# Misc.net
KiCad netlist of a schematic drawn in Altium Designer
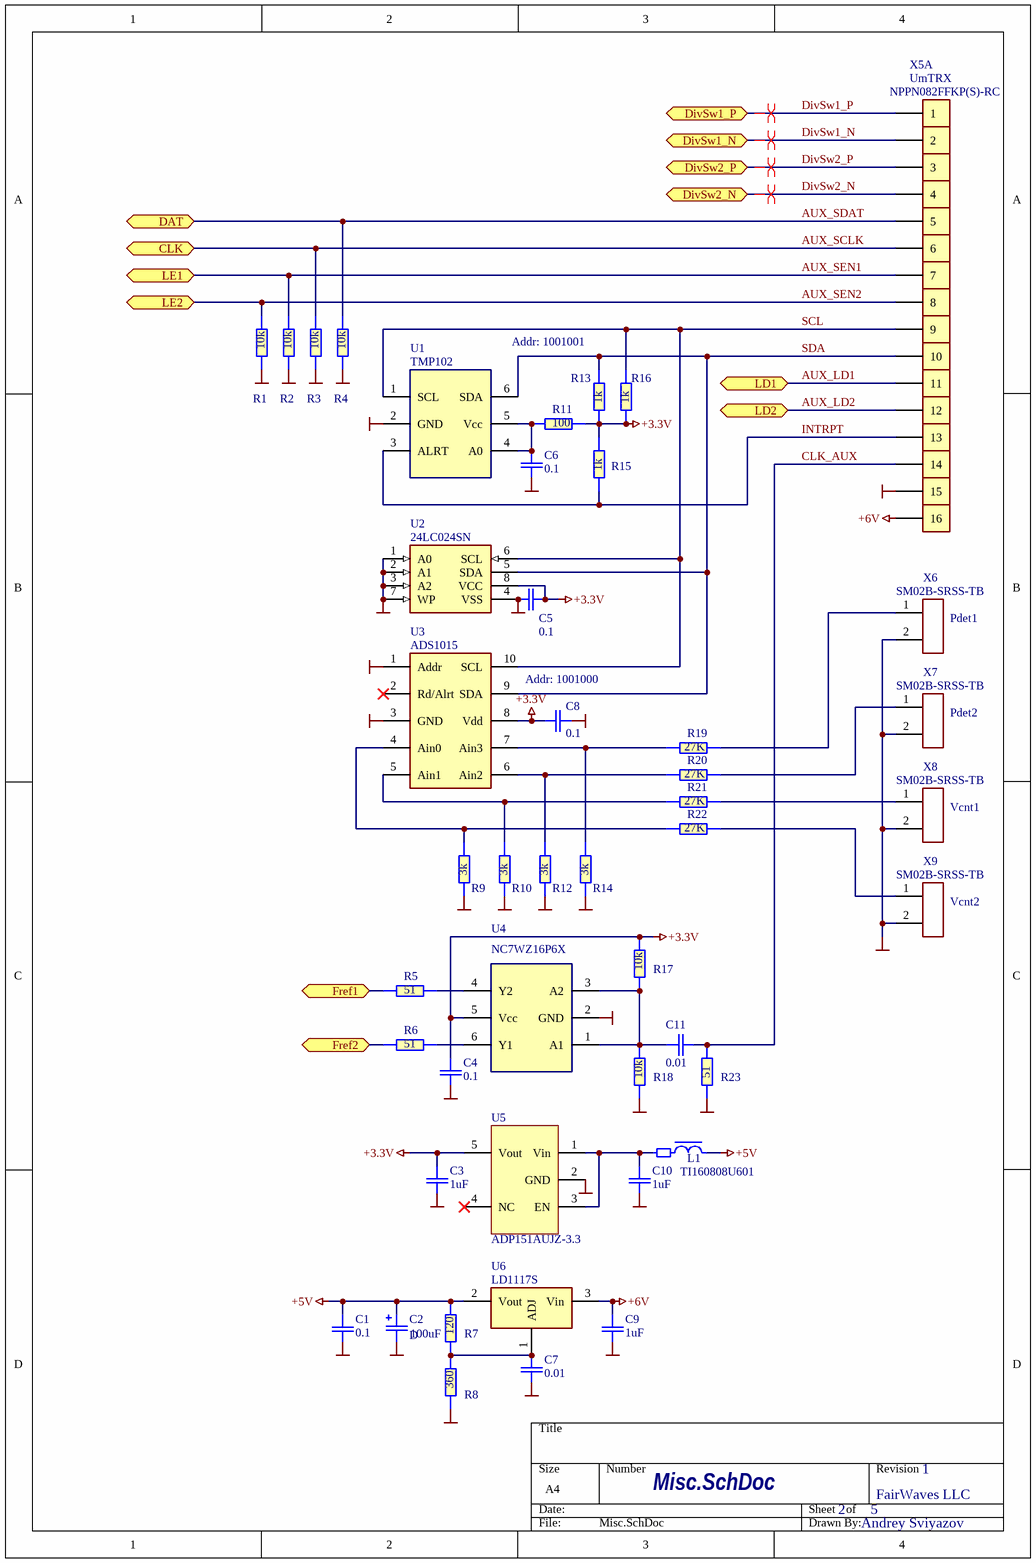
[diagram p0: Misc.SchDoc]

(export (version "E")
  (design (tool "Eeschema 10.0.6"))
  (components
    (comp (ref "C1")
      (value "0.1")
      (footprint "C0603-Phillips")
      (description "Capacitor")
      (fields (field (name "MANUFACTURER") "MURATA") (field (name "TOLERANCE") "20%"))
      (libsource (lib "Capacitors") (part "C0603"))
    )
    (comp (ref "C2")
      (value "100uF")
      (footprint "cd7343")
      (description "Capacitor")
      (fields (field (name "MANUFACTURER") "SPRAGUE"))
      (libsource (lib "altium-import") (part "root_0_mirrored_CD7343_"))
    )
    (comp (ref "C3")
      (value "1uF")
      (footprint "C0603-Phillips")
      (description "Capacitor")
      (fields (field (name "MANUFACTURER") "MURATA") (field (name "TOLERANCE") "20%"))
      (libsource (lib "Capacitors") (part "C0603"))
    )
    (comp (ref "C4")
      (value "0.1")
      (footprint "C0603-Phillips")
      (description "Capacitor")
      (fields (field (name "MANUFACTURER") "MURATA") (field (name "TOLERANCE") "20%"))
      (libsource (lib "Capacitors") (part "C0603"))
    )
    (comp (ref "C5")
      (value "0.1")
      (footprint "C0603-Phillips")
      (description "Capacitor")
      (fields (field (name "MANUFACTURER") "MURATA") (field (name "TOLERANCE") "20%"))
      (libsource (lib "Capacitors") (part "C0603"))
    )
    (comp (ref "C6")
      (value "0.1")
      (footprint "C0603-Phillips")
      (description "Capacitor")
      (fields (field (name "MANUFACTURER") "MURATA") (field (name "TOLERANCE") "20%"))
      (libsource (lib "Capacitors") (part "C0603"))
    )
    (comp (ref "C7")
      (value "0.01")
      (footprint "C0603-Phillips")
      (description "Capacitor")
      (fields (field (name "MANUFACTURER") "MURATA") (field (name "TOLERANCE") "20%"))
      (libsource (lib "Capacitors") (part "C0603"))
    )
    (comp (ref "C8")
      (value "0.1")
      (footprint "C0603-Phillips")
      (description "Capacitor")
      (fields (field (name "MANUFACTURER") "MURATA") (field (name "TOLERANCE") "20%"))
      (libsource (lib "Capacitors") (part "C0603"))
    )
    (comp (ref "C9")
      (value "1uF")
      (footprint "C0603-Phillips")
      (description "Capacitor")
      (fields (field (name "MANUFACTURER") "MURATA") (field (name "TOLERANCE") "20%"))
      (libsource (lib "Capacitors") (part "C0603"))
    )
    (comp (ref "C10")
      (value "1uF")
      (footprint "C0603-Phillips")
      (description "Capacitor")
      (fields (field (name "MANUFACTURER") "MURATA") (field (name "TOLERANCE") "20%"))
      (libsource (lib "Capacitors") (part "C0603"))
    )
    (comp (ref "C11")
      (value "0.01")
      (footprint "C0603-Phillips")
      (description "Capacitor")
      (fields (field (name "MANUFACTURER") "MURATA") (field (name "TOLERANCE") "20%"))
      (libsource (lib "Capacitors") (part "C0603"))
    )
    (comp (ref "L1")
      (value "TI160808U601")
      (footprint "Andy:Ti160808-Phillips")
      (description "Choke")
      (fields (field (name "MANUFACTURER") "MURATA"))
      (libsource (lib "altium-import") (part "root_0_mirrored_TI160808_"))
    )
    (comp (ref "R1")
      (value "10k")
      (footprint "R0603-PHILLIPS")
      (description "Resistor")
      (fields (field (name "MANUFACTURER") "YAGEO") (field (name "TOLERANCE") "5%"))
      (libsource (lib "altium-import") (part "root_2_R0603_"))
    )
    (comp (ref "R2")
      (value "10k")
      (footprint "R0603-PHILLIPS")
      (description "Resistor")
      (fields (field (name "MANUFACTURER") "YAGEO") (field (name "TOLERANCE") "5%"))
      (libsource (lib "altium-import") (part "root_2_R0603_"))
    )
    (comp (ref "R3")
      (value "10k")
      (footprint "R0603-PHILLIPS")
      (description "Resistor")
      (fields (field (name "MANUFACTURER") "YAGEO") (field (name "TOLERANCE") "5%"))
      (libsource (lib "altium-import") (part "root_2_R0603_"))
    )
    (comp (ref "R4")
      (value "10k")
      (footprint "R0603-PHILLIPS")
      (description "Resistor")
      (fields (field (name "MANUFACTURER") "YAGEO") (field (name "TOLERANCE") "5%"))
      (libsource (lib "altium-import") (part "root_2_R0603_"))
    )
    (comp (ref "R5")
      (value "51")
      (footprint "R0603-PHILLIPS")
      (description "Resistor")
      (fields (field (name "MANUFACTURER") "YAGEO") (field (name "TOLERANCE") "5%"))
      (libsource (lib "altium-import") (part "root_1_R0603_"))
    )
    (comp (ref "R6")
      (value "51")
      (footprint "R0603-PHILLIPS")
      (description "Resistor")
      (fields (field (name "MANUFACTURER") "YAGEO") (field (name "TOLERANCE") "5%"))
      (libsource (lib "altium-import") (part "root_1_R0603_"))
    )
    (comp (ref "R7")
      (value "120")
      (footprint "R0603-PHILLIPS")
      (description "Resistor")
      (fields (field (name "MANUFACTURER") "YAGEO") (field (name "TOLERANCE") "5%"))
      (libsource (lib "altium-import") (part "root_0_mirrored_R0603_"))
    )
    (comp (ref "R8")
      (value "360")
      (footprint "R0603-PHILLIPS")
      (description "Resistor")
      (fields (field (name "MANUFACTURER") "YAGEO") (field (name "TOLERANCE") "5%"))
      (libsource (lib "altium-import") (part "root_0_mirrored_R0603_"))
    )
    (comp (ref "R9")
      (value "3k")
      (footprint "R0603-PHILLIPS")
      (description "Resistor")
      (fields (field (name "MANUFACTURER") "YAGEO") (field (name "TOLERANCE") "1%"))
      (libsource (lib "altium-import") (part "root_0_mirrored_R0603_"))
    )
    (comp (ref "R10")
      (value "3k")
      (footprint "R0603-PHILLIPS")
      (description "Resistor")
      (fields (field (name "MANUFACTURER") "YAGEO") (field (name "TOLERANCE") "1%"))
      (libsource (lib "altium-import") (part "root_0_mirrored_R0603_"))
    )
    (comp (ref "R11")
      (value "100")
      (footprint "R0603-PHILLIPS")
      (description "Resistor")
      (fields (field (name "MANUFACTURER") "YAGEO") (field (name "TOLERANCE") "5%"))
      (libsource (lib "altium-import") (part "root_1_R0603_"))
    )
    (comp (ref "R12")
      (value "3k")
      (footprint "R0603-PHILLIPS")
      (description "Resistor")
      (fields (field (name "MANUFACTURER") "YAGEO") (field (name "TOLERANCE") "1%"))
      (libsource (lib "altium-import") (part "root_0_mirrored_R0603_"))
    )
    (comp (ref "R13")
      (value "1k")
      (footprint "R0603-PHILLIPS")
      (description "Resistor")
      (fields (field (name "MANUFACTURER") "YAGEO") (field (name "TOLERANCE") "5%"))
      (libsource (lib "altium-import") (part "root_2_R0603_"))
    )
    (comp (ref "R14")
      (value "3k")
      (footprint "R0603-PHILLIPS")
      (description "Resistor")
      (fields (field (name "MANUFACTURER") "YAGEO") (field (name "TOLERANCE") "1%"))
      (libsource (lib "altium-import") (part "root_0_mirrored_R0603_"))
    )
    (comp (ref "R15")
      (value "1k")
      (footprint "R0603-PHILLIPS")
      (description "Resistor")
      (fields (field (name "MANUFACTURER") "YAGEO") (field (name "TOLERANCE") "5%"))
      (libsource (lib "altium-import") (part "root_2_R0603_"))
    )
    (comp (ref "R16")
      (value "1k")
      (footprint "R0603-PHILLIPS")
      (description "Resistor")
      (fields (field (name "MANUFACTURER") "YAGEO") (field (name "TOLERANCE") "5%"))
      (libsource (lib "altium-import") (part "root_2_R0603_"))
    )
    (comp (ref "R17")
      (value "10k")
      (footprint "R0603-PHILLIPS")
      (description "Resistor")
      (fields (field (name "MANUFACTURER") "YAGEO") (field (name "TOLERANCE") "5%"))
      (libsource (lib "altium-import") (part "root_0_mirrored_R0603_"))
    )
    (comp (ref "R18")
      (value "10k")
      (footprint "R0603-PHILLIPS")
      (description "Resistor")
      (fields (field (name "MANUFACTURER") "YAGEO") (field (name "TOLERANCE") "5%"))
      (libsource (lib "altium-import") (part "root_0_mirrored_R0603_"))
    )
    (comp (ref "R19")
      (value "27K")
      (footprint "R0603-PHILLIPS")
      (description "Resistor")
      (fields (field (name "MANUFACTURER") "YAGEO") (field (name "TOLERANCE") "1%"))
      (libsource (lib "altium-import") (part "root_1_R0603_"))
    )
    (comp (ref "R20")
      (value "27K")
      (footprint "R0603-PHILLIPS")
      (description "Resistor")
      (fields (field (name "MANUFACTURER") "YAGEO") (field (name "TOLERANCE") "1%"))
      (libsource (lib "altium-import") (part "root_1_R0603_"))
    )
    (comp (ref "R21")
      (value "27K")
      (footprint "R0603-PHILLIPS")
      (description "Resistor")
      (fields (field (name "MANUFACTURER") "YAGEO") (field (name "TOLERANCE") "1%"))
      (libsource (lib "altium-import") (part "root_1_R0603_"))
    )
    (comp (ref "R22")
      (value "27K")
      (footprint "R0603-PHILLIPS")
      (description "Resistor")
      (fields (field (name "MANUFACTURER") "YAGEO") (field (name "TOLERANCE") "1%"))
      (libsource (lib "altium-import") (part "root_1_R0603_"))
    )
    (comp (ref "R23")
      (value "51")
      (footprint "R0603-PHILLIPS")
      (description "Resistor")
      (fields (field (name "MANUFACTURER") "YAGEO") (field (name "TOLERANCE") "5%"))
      (libsource (lib "altium-import") (part "root_0_mirrored_R0603_"))
    )
    (comp (ref "U1")
      (value "TMP102")
      (footprint "PDSO-G6")
      (description "IC")
      (fields (field (name "MANUFACTURER") "TI") (field (name "ADDR") "1001001"))
      (libsource (lib "Andy") (part "TMP102"))
    )
    (comp (ref "U2")
      (value "24LC024SN")
      (footprint "FootSO-DIP:SOIC8")
      (description "EEPROM")
      (fields (field (name "MANUFACTURER") "Microchip"))
      (libsource (lib "MicroCircuits0-L") (part "AT24CXX"))
    )
    (comp (ref "U3")
      (value "ADS1015")
      (footprint "TSSOP-SPDSO-G10")
      (description "IC")
      (fields (field (name "MANUFACTURER") "TI") (field (name "ADDR") "1001000"))
      (libsource (lib "Andy") (part "ADS1015"))
    )
    (comp (ref "U4")
      (value "NC7WZ16P6X")
      (footprint "SC70-6LD(SOT363)")
      (description "IC")
      (fields (field (name "MANUFACTURER") "Fairchild"))
      (libsource (lib "Andy") (part "NC7WZ16P6X"))
    )
    (comp (ref "U5")
      (value "ADP151AUJZ-3.3")
      (footprint "SOT-23-5[3.1x1.8/0.95]")
      (description "IC")
      (fields (field (name "MANUFACTURER") "AD"))
      (libsource (lib "Andy") (part "ADP151AUJZ"))
    )
    (comp (ref "U6")
      (value "LD1117S")
      (footprint "Foot3-4pins:SOT-223-1")
      (description "IC")
      (fields (field (name "MANUFACTURER") "STMicro"))
      (libsource (lib "altium-import") (part "root_0_mirrored_LD1117ADJ_"))
    )
    (comp (ref "X5")
      (value "NPPN082FFKP(S)-RC")
      (footprint "NPPN082FFKP(S)")
      (description "Connector female 2mm SMD")
      (fields (field (name "MANUFACTURER") "Sullins") (field (name "MISC") "UmTRX"))
      (libsource (lib "Andy") (part "NPPN082FFKP(S)"))
    )
    (comp (ref "X6")
      (value "SM02B-SRSS-TB")
      (footprint "SM02B-SRSS-TB")
      (description "Connector")
      (fields (field (name "MANUFACTURER") "JST") (field (name "MISC") "Pdet1"))
      (libsource (lib "Andy") (part "SM02B-SRSS-TB"))
    )
    (comp (ref "X7")
      (value "SM02B-SRSS-TB")
      (footprint "SM02B-SRSS-TB")
      (description "Connector")
      (fields (field (name "MANUFACTURER") "JST") (field (name "MISC") "Pdet2"))
      (libsource (lib "Andy") (part "SM02B-SRSS-TB"))
    )
    (comp (ref "X8")
      (value "SM02B-SRSS-TB")
      (footprint "SM02B-SRSS-TB")
      (description "Connector")
      (fields (field (name "MANUFACTURER") "JST") (field (name "MISC") "Vcnt1"))
      (libsource (lib "Andy") (part "SM02B-SRSS-TB"))
    )
    (comp (ref "X9")
      (value "SM02B-SRSS-TB")
      (footprint "SM02B-SRSS-TB")
      (description "Connector")
      (fields (field (name "MANUFACTURER") "JST") (field (name "MISC") "Vcnt2"))
      (libsource (lib "Andy") (part "SM02B-SRSS-TB"))
    )
  )
  (nets
    (net (code "1") (name "+3.3V") (class "Default")
      (node (ref "C3") (pin "2") (pinfunction "2_2") (pintype "passive"))
      (node (ref "C4") (pin "2") (pinfunction "2_2") (pintype "passive"))
      (node (ref "C5") (pin "2") (pinfunction "2_2") (pintype "passive"))
      (node (ref "C8") (pin "1") (pinfunction "1_1") (pintype "passive"))
      (node (ref "R11") (pin "2") (pinfunction "2_2") (pintype "passive"))
      (node (ref "R13") (pin "1") (pinfunction "1_1") (pintype "passive"))
      (node (ref "R15") (pin "2") (pinfunction "2_2") (pintype "passive"))
      (node (ref "R16") (pin "1") (pinfunction "1_1") (pintype "passive"))
      (node (ref "R17") (pin "1") (pinfunction "1_1") (pintype "passive"))
      (node (ref "U2") (pin "8") (pinfunction "VCC_8") (pintype "power_in"))
      (node (ref "U3") (pin "8") (pinfunction "Vdd_8") (pintype "passive"))
      (node (ref "U4") (pin "5") (pinfunction "Vcc_5") (pintype "passive"))
      (node (ref "U5") (pin "5") (pinfunction "Vout_5") (pintype "passive"))
    )
    (net (code "2") (name "+5V") (class "Default")
      (node (ref "C1") (pin "2") (pinfunction "2_2") (pintype "passive"))
      (node (ref "C2") (pin "1") (pinfunction "+_1") (pintype "passive"))
      (node (ref "L1") (pin "1") (pinfunction "1_1") (pintype "passive"))
      (node (ref "R7") (pin "1") (pinfunction "1_1") (pintype "passive"))
      (node (ref "U6") (pin "2") (pinfunction "Vout_2") (pintype "passive"))
    )
    (net (code "3") (name "+6V") (class "Default")
      (node (ref "C9") (pin "2") (pinfunction "2_2") (pintype "passive"))
      (node (ref "U6") (pin "3") (pinfunction "Vin_3") (pintype "passive"))
      (node (ref "X5") (pin "16") (pinfunction "16_16") (pintype "passive"))
    )
    (net (code "4") (name "/AUX_LD1") (class "Default")
      (node (ref "X5") (pin "11") (pinfunction "11_11") (pintype "passive"))
    )
    (net (code "5") (name "/AUX_LD2") (class "Default")
      (node (ref "X5") (pin "12") (pinfunction "12_12") (pintype "passive"))
    )
    (net (code "6") (name "/AUX_SCLK") (class "Default")
      (node (ref "R3") (pin "2") (pinfunction "2_2") (pintype "passive"))
      (node (ref "X5") (pin "6") (pinfunction "6_6") (pintype "passive"))
    )
    (net (code "7") (name "/AUX_SDAT") (class "Default")
      (node (ref "R4") (pin "2") (pinfunction "2_2") (pintype "passive"))
      (node (ref "X5") (pin "5") (pinfunction "5_5") (pintype "passive"))
    )
    (net (code "8") (name "/AUX_SEN1") (class "Default")
      (node (ref "R2") (pin "2") (pinfunction "2_2") (pintype "passive"))
      (node (ref "X5") (pin "7") (pinfunction "7_7") (pintype "passive"))
    )
    (net (code "9") (name "/AUX_SEN2") (class "Default")
      (node (ref "R1") (pin "2") (pinfunction "2_2") (pintype "passive"))
      (node (ref "X5") (pin "8") (pinfunction "8_8") (pintype "passive"))
    )
    (net (code "10") (name "/CLK_AUX") (class "Default")
      (node (ref "C11") (pin "1") (pinfunction "1_1") (pintype "passive"))
      (node (ref "R23") (pin "1") (pinfunction "1_1") (pintype "passive"))
      (node (ref "X5") (pin "14") (pinfunction "14_14") (pintype "passive"))
    )
    (net (code "11") (name "/DivSw1_N") (class "Default")
      (node (ref "X5") (pin "2") (pinfunction "2_2") (pintype "passive"))
    )
    (net (code "12") (name "/DivSw1_P") (class "Default")
      (node (ref "X5") (pin "1") (pinfunction "1_1") (pintype "passive"))
    )
    (net (code "13") (name "/DivSw2_N") (class "Default")
      (node (ref "X5") (pin "4") (pinfunction "4_4") (pintype "passive"))
    )
    (net (code "14") (name "/DivSw2_P") (class "Default")
      (node (ref "X5") (pin "3") (pinfunction "3_3") (pintype "passive"))
    )
    (net (code "15") (name "/Fref1") (class "Default")
      (node (ref "R5") (pin "1") (pinfunction "1_1") (pintype "passive"))
    )
    (net (code "16") (name "/Fref2") (class "Default")
      (node (ref "R6") (pin "1") (pinfunction "1_1") (pintype "passive"))
    )
    (net (code "17") (name "/INTRPT") (class "Default")
      (node (ref "R15") (pin "1") (pinfunction "1_1") (pintype "passive"))
      (node (ref "U1") (pin "3") (pinfunction "ALRT_3") (pintype "passive"))
      (node (ref "X5") (pin "13") (pinfunction "13_13") (pintype "passive"))
    )
    (net (code "18") (name "/SCL") (class "Default")
      (node (ref "R16") (pin "2") (pinfunction "2_2") (pintype "passive"))
      (node (ref "U1") (pin "1") (pinfunction "SCL_1") (pintype "passive"))
      (node (ref "U2") (pin "6") (pinfunction "SCL_6") (pintype "input"))
      (node (ref "U3") (pin "10") (pinfunction "SCL_10") (pintype "passive"))
      (node (ref "X5") (pin "9") (pinfunction "9_9") (pintype "passive"))
    )
    (net (code "19") (name "/SDA") (class "Default")
      (node (ref "R13") (pin "2") (pinfunction "2_2") (pintype "passive"))
      (node (ref "U1") (pin "6") (pinfunction "SDA_6") (pintype "passive"))
      (node (ref "U2") (pin "5") (pinfunction "SDA_5") (pintype "passive"))
      (node (ref "U3") (pin "9") (pinfunction "SDA_9") (pintype "passive"))
      (node (ref "X5") (pin "10") (pinfunction "10_10") (pintype "passive"))
    )
    (net (code "20") (name "GND") (class "Default")
      (node (ref "C1") (pin "1") (pinfunction "1_1") (pintype "passive"))
      (node (ref "C10") (pin "1") (pinfunction "1_1") (pintype "passive"))
      (node (ref "C2") (pin "2") (pinfunction "-_2") (pintype "passive"))
      (node (ref "C3") (pin "1") (pinfunction "1_1") (pintype "passive"))
      (node (ref "C4") (pin "1") (pinfunction "1_1") (pintype "passive"))
      (node (ref "C5") (pin "1") (pinfunction "1_1") (pintype "passive"))
      (node (ref "C6") (pin "1") (pinfunction "1_1") (pintype "passive"))
      (node (ref "C7") (pin "1") (pinfunction "1_1") (pintype "passive"))
      (node (ref "C8") (pin "2") (pinfunction "2_2") (pintype "passive"))
      (node (ref "C9") (pin "1") (pinfunction "1_1") (pintype "passive"))
      (node (ref "R1") (pin "1") (pinfunction "1_1") (pintype "passive"))
      (node (ref "R10") (pin "2") (pinfunction "2_2") (pintype "passive"))
      (node (ref "R12") (pin "2") (pinfunction "2_2") (pintype "passive"))
      (node (ref "R14") (pin "2") (pinfunction "2_2") (pintype "passive"))
      (node (ref "R18") (pin "2") (pinfunction "2_2") (pintype "passive"))
      (node (ref "R2") (pin "1") (pinfunction "1_1") (pintype "passive"))
      (node (ref "R23") (pin "2") (pinfunction "2_2") (pintype "passive"))
      (node (ref "R3") (pin "1") (pinfunction "1_1") (pintype "passive"))
      (node (ref "R4") (pin "1") (pinfunction "1_1") (pintype "passive"))
      (node (ref "R8") (pin "2") (pinfunction "2_2") (pintype "passive"))
      (node (ref "R9") (pin "2") (pinfunction "2_2") (pintype "passive"))
      (node (ref "U1") (pin "2") (pinfunction "GND_2") (pintype "passive"))
      (node (ref "U2") (pin "1") (pinfunction "A0_1") (pintype "input"))
      (node (ref "U2") (pin "2") (pinfunction "A1_2") (pintype "input"))
      (node (ref "U2") (pin "3") (pinfunction "A2_3") (pintype "input"))
      (node (ref "U2") (pin "4") (pinfunction "VSS_4") (pintype "power_in"))
      (node (ref "U2") (pin "7") (pinfunction "WP_7") (pintype "input"))
      (node (ref "U3") (pin "1") (pinfunction "Addr_1") (pintype "passive"))
      (node (ref "U3") (pin "3") (pinfunction "GND_3") (pintype "passive"))
      (node (ref "U4") (pin "2") (pinfunction "GND_2") (pintype "passive"))
      (node (ref "U5") (pin "2") (pinfunction "GND_2") (pintype "passive"))
      (node (ref "X5") (pin "15") (pinfunction "15_15") (pintype "passive"))
      (node (ref "X6") (pin "2") (pinfunction "2_2") (pintype "passive"))
      (node (ref "X7") (pin "2") (pinfunction "2_2") (pintype "passive"))
      (node (ref "X8") (pin "2") (pinfunction "2_2") (pintype "passive"))
      (node (ref "X9") (pin "2") (pinfunction "2_2") (pintype "passive"))
    )
    (net (code "21") (name "Net-(R19-Pad2)") (class "Default")
      (node (ref "R19") (pin "2") (pinfunction "2_2") (pintype "passive"))
      (node (ref "X6") (pin "1") (pinfunction "1_1") (pintype "passive"))
    )
    (net (code "22") (name "Net-(R20-Pad2)") (class "Default")
      (node (ref "R20") (pin "2") (pinfunction "2_2") (pintype "passive"))
      (node (ref "X7") (pin "1") (pinfunction "1_1") (pintype "passive"))
    )
    (net (code "23") (name "Net-(R21-Pad2)") (class "Default")
      (node (ref "R21") (pin "2") (pinfunction "2_2") (pintype "passive"))
      (node (ref "X8") (pin "1") (pinfunction "1_1") (pintype "passive"))
    )
    (net (code "24") (name "Net-(R22-Pad2)") (class "Default")
      (node (ref "R22") (pin "2") (pinfunction "2_2") (pintype "passive"))
      (node (ref "X9") (pin "1") (pinfunction "1_1") (pintype "passive"))
    )
    (net (code "25") (name "Net-(U1-A0)") (class "Default")
      (node (ref "C6") (pin "2") (pinfunction "2_2") (pintype "passive"))
      (node (ref "R11") (pin "1") (pinfunction "1_1") (pintype "passive"))
      (node (ref "U1") (pin "4") (pinfunction "A0_4") (pintype "passive"))
      (node (ref "U1") (pin "5") (pinfunction "Vcc_5") (pintype "passive"))
    )
    (net (code "26") (name "Net-(U3-Ain0)") (class "Default")
      (node (ref "R22") (pin "1") (pinfunction "1_1") (pintype "passive"))
      (node (ref "R9") (pin "1") (pinfunction "1_1") (pintype "passive"))
      (node (ref "U3") (pin "4") (pinfunction "Ain0_4") (pintype "passive"))
    )
    (net (code "27") (name "Net-(U3-Ain1)") (class "Default")
      (node (ref "R10") (pin "1") (pinfunction "1_1") (pintype "passive"))
      (node (ref "R21") (pin "1") (pinfunction "1_1") (pintype "passive"))
      (node (ref "U3") (pin "5") (pinfunction "Ain1_5") (pintype "passive"))
    )
    (net (code "28") (name "Net-(U3-Ain2)") (class "Default")
      (node (ref "R12") (pin "1") (pinfunction "1_1") (pintype "passive"))
      (node (ref "R20") (pin "1") (pinfunction "1_1") (pintype "passive"))
      (node (ref "U3") (pin "6") (pinfunction "Ain2_6") (pintype "passive"))
    )
    (net (code "29") (name "Net-(U3-Ain3)") (class "Default")
      (node (ref "R14") (pin "1") (pinfunction "1_1") (pintype "passive"))
      (node (ref "R19") (pin "1") (pinfunction "1_1") (pintype "passive"))
      (node (ref "U3") (pin "7") (pinfunction "Ain3_7") (pintype "passive"))
    )
    (net (code "30") (name "Net-(U4-A1)") (class "Default")
      (node (ref "C11") (pin "2") (pinfunction "2_2") (pintype "passive"))
      (node (ref "R17") (pin "2") (pinfunction "2_2") (pintype "passive"))
      (node (ref "R18") (pin "1") (pinfunction "1_1") (pintype "passive"))
      (node (ref "U4") (pin "1") (pinfunction "A1_1") (pintype "passive"))
      (node (ref "U4") (pin "3") (pinfunction "A2_3") (pintype "passive"))
    )
    (net (code "31") (name "Net-(U4-Y1)") (class "Default")
      (node (ref "R6") (pin "2") (pinfunction "2_2") (pintype "passive"))
      (node (ref "U4") (pin "6") (pinfunction "Y1_6") (pintype "passive"))
    )
    (net (code "32") (name "Net-(U4-Y2)") (class "Default")
      (node (ref "R5") (pin "2") (pinfunction "2_2") (pintype "passive"))
      (node (ref "U4") (pin "4") (pinfunction "Y2_4") (pintype "passive"))
    )
    (net (code "33") (name "Net-(U5-EN)") (class "Default")
      (node (ref "C10") (pin "2") (pinfunction "2_2") (pintype "passive"))
      (node (ref "L1") (pin "2") (pinfunction "2_2") (pintype "passive"))
      (node (ref "U5") (pin "1") (pinfunction "Vin_1") (pintype "passive"))
      (node (ref "U5") (pin "3") (pinfunction "EN_3") (pintype "passive"))
    )
    (net (code "34") (name "Net-(U6-ADJ)") (class "Default")
      (node (ref "C7") (pin "2") (pinfunction "2_2") (pintype "passive"))
      (node (ref "R7") (pin "2") (pinfunction "2_2") (pintype "passive"))
      (node (ref "R8") (pin "1") (pinfunction "1_1") (pintype "passive"))
      (node (ref "U6") (pin "1") (pinfunction "ADJ_1") (pintype "passive"))
    )
    (net (code "35") (name "unconnected-(U3-Rd{slash}Alrt-Pad2)") (class "Default")
      (node (ref "U3") (pin "2") (pinfunction "Rd/Alrt_2") (pintype "passive+no_connect"))
    )
    (net (code "36") (name "unconnected-(U5-NC-Pad4)") (class "Default")
      (node (ref "U5") (pin "4") (pinfunction "NC_4") (pintype "passive+no_connect"))
    )
  )
)
